# Comparator.net
KiCad netlist of a schematic drawn in Altium Designer
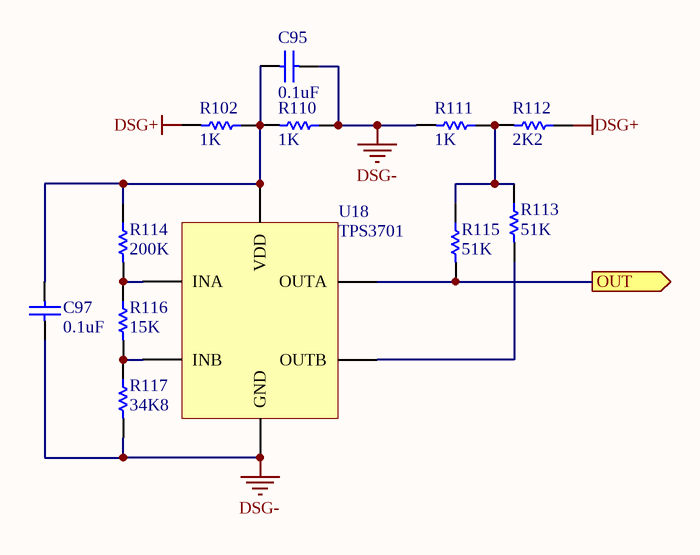
[diagram p0: Comparator.SchDoc]

(export (version "E")
  (design (tool "Eeschema 10.0.6"))
  (components
    (comp (ref "C95")
      (value "0.1uF")
      (footprint "C0603[1608X92]")
      (description "0.1uF 100V 10% 0603 (1608 Metric)")
      (fields (field (name "PARTNUMBER") "GRM188R72A104KA35D") (field (name "MANUFACTURER") "Murata"))
      (libsource (lib "Capacitors") (part "CAP_0.1uF_100V_0603_10%"))
    )
    (comp (ref "C97")
      (value "0.1uF")
      (footprint "C0603[1608X92]")
      (description "0.1uF 100V 10% 0603 (1608 Metric)")
      (fields (field (name "PARTNUMBER") "GRM188R72A104KA35D") (field (name "MANUFACTURER") "Murata"))
      (libsource (lib "Capacitors") (part "CAP_0.1uF_100V_0603_10%"))
    )
    (comp (ref "R102")
      (value "1K")
      (footprint "R0603[1608]")
      (description "1K 0.25W 1% 0603 (1005 Metric)")
      (fields (field (name "MANUFACTURER") "Vishay / Dale") (field (name "PARTNUMBER") "CRCW06031K00FKEAHP"))
      (libsource (lib "Resistors") (part "RES_1K_0603_1%"))
    )
    (comp (ref "R110")
      (value "1K")
      (footprint "R0603[1608]")
      (description "1K 0.25W 1% 0603 (1005 Metric)")
      (fields (field (name "MANUFACTURER") "Vishay / Dale") (field (name "PARTNUMBER") "CRCW06031K00FKEAHP"))
      (libsource (lib "Resistors") (part "RES_1K_0603_1%"))
    )
    (comp (ref "R111")
      (value "1K")
      (footprint "R0603[1608]")
      (description "1K 0.25W 1% 0603 (1005 Metric)")
      (fields (field (name "MANUFACTURER") "Vishay / Dale") (field (name "PARTNUMBER") "CRCW06031K00FKEAHP"))
      (libsource (lib "Resistors") (part "RES_1K_0603_1%"))
    )
    (comp (ref "R112")
      (value "2K2")
      (footprint "R0603[1608]")
      (description "2K2 0.25W 1% 0603 (1005 Metric)")
      (fields (field (name "MANUFACTURER") "Vishay / Dale") (field (name "PARTNUMBER") "CRCW06032K20FKEAHP"))
      (libsource (lib "Resistors") (part "RES_2K2_0603_1%"))
    )
    (comp (ref "R113")
      (value "51K")
      (footprint "R0603[1608]")
      (description "51K 0.25W 1% 0603 (1005 Metric)")
      (fields (field (name "MANUFACTURER") "Panasonic") (field (name "PARTNUMBER") "ERJ-PA3F5102V"))
      (libsource (lib "Resistors") (part "RES_51K_0603_1%"))
    )
    (comp (ref "R114")
      (value "200K")
      (footprint "R0603[1608]")
      (description "200K 0.25W 1% 0603 (1005 Metric)")
      (fields (field (name "MANUFACTURER") "Rohm Semiconductor") (field (name "PARTNUMBER") "ESR03EZPJ204"))
      (libsource (lib "Resistors") (part "RES_200K_0603_1%"))
    )
    (comp (ref "R115")
      (value "51K")
      (footprint "R0603[1608]")
      (description "51K 0.25W 1% 0603 (1005 Metric)")
      (fields (field (name "MANUFACTURER") "Panasonic") (field (name "PARTNUMBER") "ERJ-PA3F5102V"))
      (libsource (lib "Resistors") (part "RES_51K_0603_1%"))
    )
    (comp (ref "R116")
      (value "15K")
      (footprint "R0603[1608]")
      (description "15K 0.25W 1% 0603 (1005 Metric)")
      (fields (field (name "MANUFACTURER") "Vishay / Dale") (field (name "PARTNUMBER") "CRCW060315K0FKEAHP"))
      (libsource (lib "Resistors") (part "RES_15K_0603_1%"))
    )
    (comp (ref "R117")
      (value "34K8")
      (footprint "R0603[1608]")
      (description "34K8 0.1W 1% 0603 (1005 Metric)")
      (fields (field (name "MANUFACTURER") "Panasonic") (field (name "PARTNUMBER") "ERJ-3EKF3482V"))
      (libsource (lib "Resistors") (part "RES_34K8_0603_1%"))
    )
    (comp (ref "U18")
      (value "TPS3701")
      (footprint "SOT-23-6")
      (fields (field (name "MANUFACTURER") "Texas Instruments"))
      (libsource (lib "ICs") (part "TPS3701"))
    )
  )
  (nets
    (net (code "1") (name "/OUT") (class "Default")
      (node (ref "R115") (pin "1") (pinfunction "1_1") (pintype "passive"))
      (node (ref "U18") (pin "1") (pinfunction "OUTA_1") (pintype "passive"))
    )
    (net (code "2") (name "DSG+") (class "Default")
      (node (ref "R102") (pin "1") (pinfunction "1_1") (pintype "passive"))
      (node (ref "R112") (pin "2") (pinfunction "2_2") (pintype "passive"))
    )
    (net (code "3") (name "DSG-") (class "Default")
      (node (ref "C95") (pin "2") (pinfunction "2_2") (pintype "passive"))
      (node (ref "C97") (pin "1") (pinfunction "1_1") (pintype "passive"))
      (node (ref "R110") (pin "2") (pinfunction "2_2") (pintype "passive"))
      (node (ref "R111") (pin "1") (pinfunction "1_1") (pintype "passive"))
      (node (ref "R117") (pin "1") (pinfunction "1_1") (pintype "passive"))
      (node (ref "U18") (pin "2") (pinfunction "GND_2") (pintype "power_in"))
    )
    (net (code "4") (name "Net-(R111-Pad2)") (class "Default")
      (node (ref "R111") (pin "2") (pinfunction "2_2") (pintype "passive"))
      (node (ref "R112") (pin "1") (pinfunction "1_1") (pintype "passive"))
      (node (ref "R113") (pin "2") (pinfunction "2_2") (pintype "passive"))
      (node (ref "R115") (pin "2") (pinfunction "2_2") (pintype "passive"))
    )
    (net (code "5") (name "Net-(U18-INA)") (class "Default")
      (node (ref "R114") (pin "1") (pinfunction "1_1") (pintype "passive"))
      (node (ref "R116") (pin "2") (pinfunction "2_2") (pintype "passive"))
      (node (ref "U18") (pin "3") (pinfunction "INA_3") (pintype "passive"))
    )
    (net (code "6") (name "Net-(U18-INB)") (class "Default")
      (node (ref "R116") (pin "1") (pinfunction "1_1") (pintype "passive"))
      (node (ref "R117") (pin "2") (pinfunction "2_2") (pintype "passive"))
      (node (ref "U18") (pin "4") (pinfunction "INB_4") (pintype "passive"))
    )
    (net (code "7") (name "Net-(U18-OUTB)") (class "Default")
      (node (ref "R113") (pin "1") (pinfunction "1_1") (pintype "passive"))
      (node (ref "U18") (pin "6") (pinfunction "OUTB_6") (pintype "passive"))
    )
    (net (code "8") (name "Net-(U18-VDD)") (class "Default")
      (node (ref "C95") (pin "1") (pinfunction "1_1") (pintype "passive"))
      (node (ref "C97") (pin "2") (pinfunction "2_2") (pintype "passive"))
      (node (ref "R102") (pin "2") (pinfunction "2_2") (pintype "passive"))
      (node (ref "R110") (pin "1") (pinfunction "1_1") (pintype "passive"))
      (node (ref "R114") (pin "2") (pinfunction "2_2") (pintype "passive"))
      (node (ref "U18") (pin "5") (pinfunction "VDD_5") (pintype "power_in"))
    )
  )
)
